# inputs.net
KiCad netlist of a schematic drawn in Altium Designer
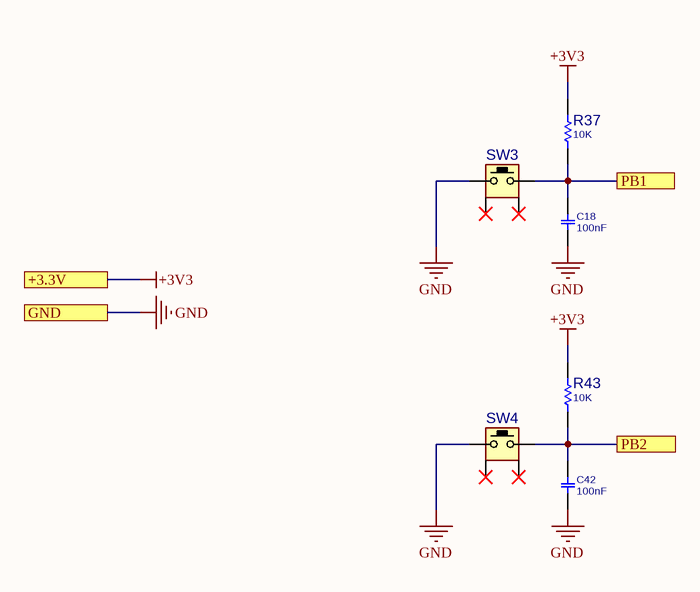
[diagram p0: inputs.SchDoc]

(export (version "E")
  (design (tool "Eeschema 10.0.6"))
  (components
    (comp (ref "C18")
      (value "100nF")
      (footprint "C0805")
      (description "CAP, MLCC, -F, -V, MATERIAL, -%, 0201")
      (fields (field (name "MANF_P#") "MANF_PART#"))
      (libsource (lib "passive_smd") (part "CAP_SMD_MLCC_0805"))
    )
    (comp (ref "C42")
      (value "100nF")
      (footprint "C0805")
      (description "CAP, MLCC, -F, -V, MATERIAL, -%, 0201")
      (fields (field (name "MANF_P#") "MANF_PART#"))
      (libsource (lib "passive_smd") (part "CAP_SMD_MLCC_0805"))
    )
    (comp (ref "R37")
      (value "10K")
      (footprint "R0805")
      (description "RESISTOR, SMD")
      (libsource (lib "passive_smd") (part "RES_SMD_0805"))
    )
    (comp (ref "R43")
      (value "10K")
      (footprint "R0805")
      (description "RESISTOR, SMD")
      (libsource (lib "passive_smd") (part "RES_SMD_0805"))
    )
    (comp (ref "SW3")
      (value "PUSHBUTTON")
      (footprint "SWPBT_SPST_R_6X6X10")
      (description "SWITCH, PUSH BUTTON, TACTILE, THD, SPST, RIGHT")
      (libsource (lib "switch_tact_PUSHB") (part "SWPBT_SPST_R_6X6X10"))
    )
    (comp (ref "SW4")
      (value "PUSHBUTTON")
      (footprint "SWPBT_SPST_R_6X6X10")
      (description "SWITCH, PUSH BUTTON, TACTILE, THD, SPST, RIGHT")
      (libsource (lib "switch_tact_PUSHB") (part "SWPBT_SPST_R_6X6X10"))
    )
  )
  (nets
    (net (code "1") (name "+3V3") (class "Default")
      (node (ref "R37") (pin "1") (pinfunction "1_1") (pintype "passive"))
      (node (ref "R43") (pin "1") (pinfunction "1_1") (pintype "passive"))
    )
    (net (code "2") (name "/PB1") (class "Default")
      (node (ref "C18") (pin "2") (pinfunction "2_2") (pintype "passive"))
      (node (ref "R37") (pin "2") (pinfunction "2_2") (pintype "passive"))
      (node (ref "SW3") (pin "2") (pinfunction "2_2") (pintype "passive"))
    )
    (net (code "3") (name "/PB2") (class "Default")
      (node (ref "C42") (pin "2") (pinfunction "2_2") (pintype "passive"))
      (node (ref "R43") (pin "2") (pinfunction "2_2") (pintype "passive"))
      (node (ref "SW4") (pin "2") (pinfunction "2_2") (pintype "passive"))
    )
    (net (code "4") (name "GND") (class "Default")
      (node (ref "C18") (pin "1") (pinfunction "1_1") (pintype "passive"))
      (node (ref "C42") (pin "1") (pinfunction "1_1") (pintype "passive"))
      (node (ref "SW3") (pin "1") (pinfunction "1_1") (pintype "passive"))
      (node (ref "SW4") (pin "1") (pinfunction "1_1") (pintype "passive"))
    )
    (net (code "5") (name "unconnected-(SW3-PadMH1)") (class "Default")
      (node (ref "SW3") (pin "MH1") (pinfunction "MH1_MH1") (pintype "passive+no_connect"))
    )
    (net (code "6") (name "unconnected-(SW3-PadMH2)") (class "Default")
      (node (ref "SW3") (pin "MH2") (pinfunction "MH2_MH2") (pintype "passive+no_connect"))
    )
    (net (code "7") (name "unconnected-(SW4-PadMH1)") (class "Default")
      (node (ref "SW4") (pin "MH1") (pinfunction "MH1_MH1") (pintype "passive+no_connect"))
    )
    (net (code "8") (name "unconnected-(SW4-PadMH2)") (class "Default")
      (node (ref "SW4") (pin "MH2") (pinfunction "MH2_MH2") (pintype "passive+no_connect"))
    )
  )
)
